# S7CAS-PLEIADES-CARTE-MERE_P01_DDR3.net
KiCad netlist of a schematic drawn in Altium Designer
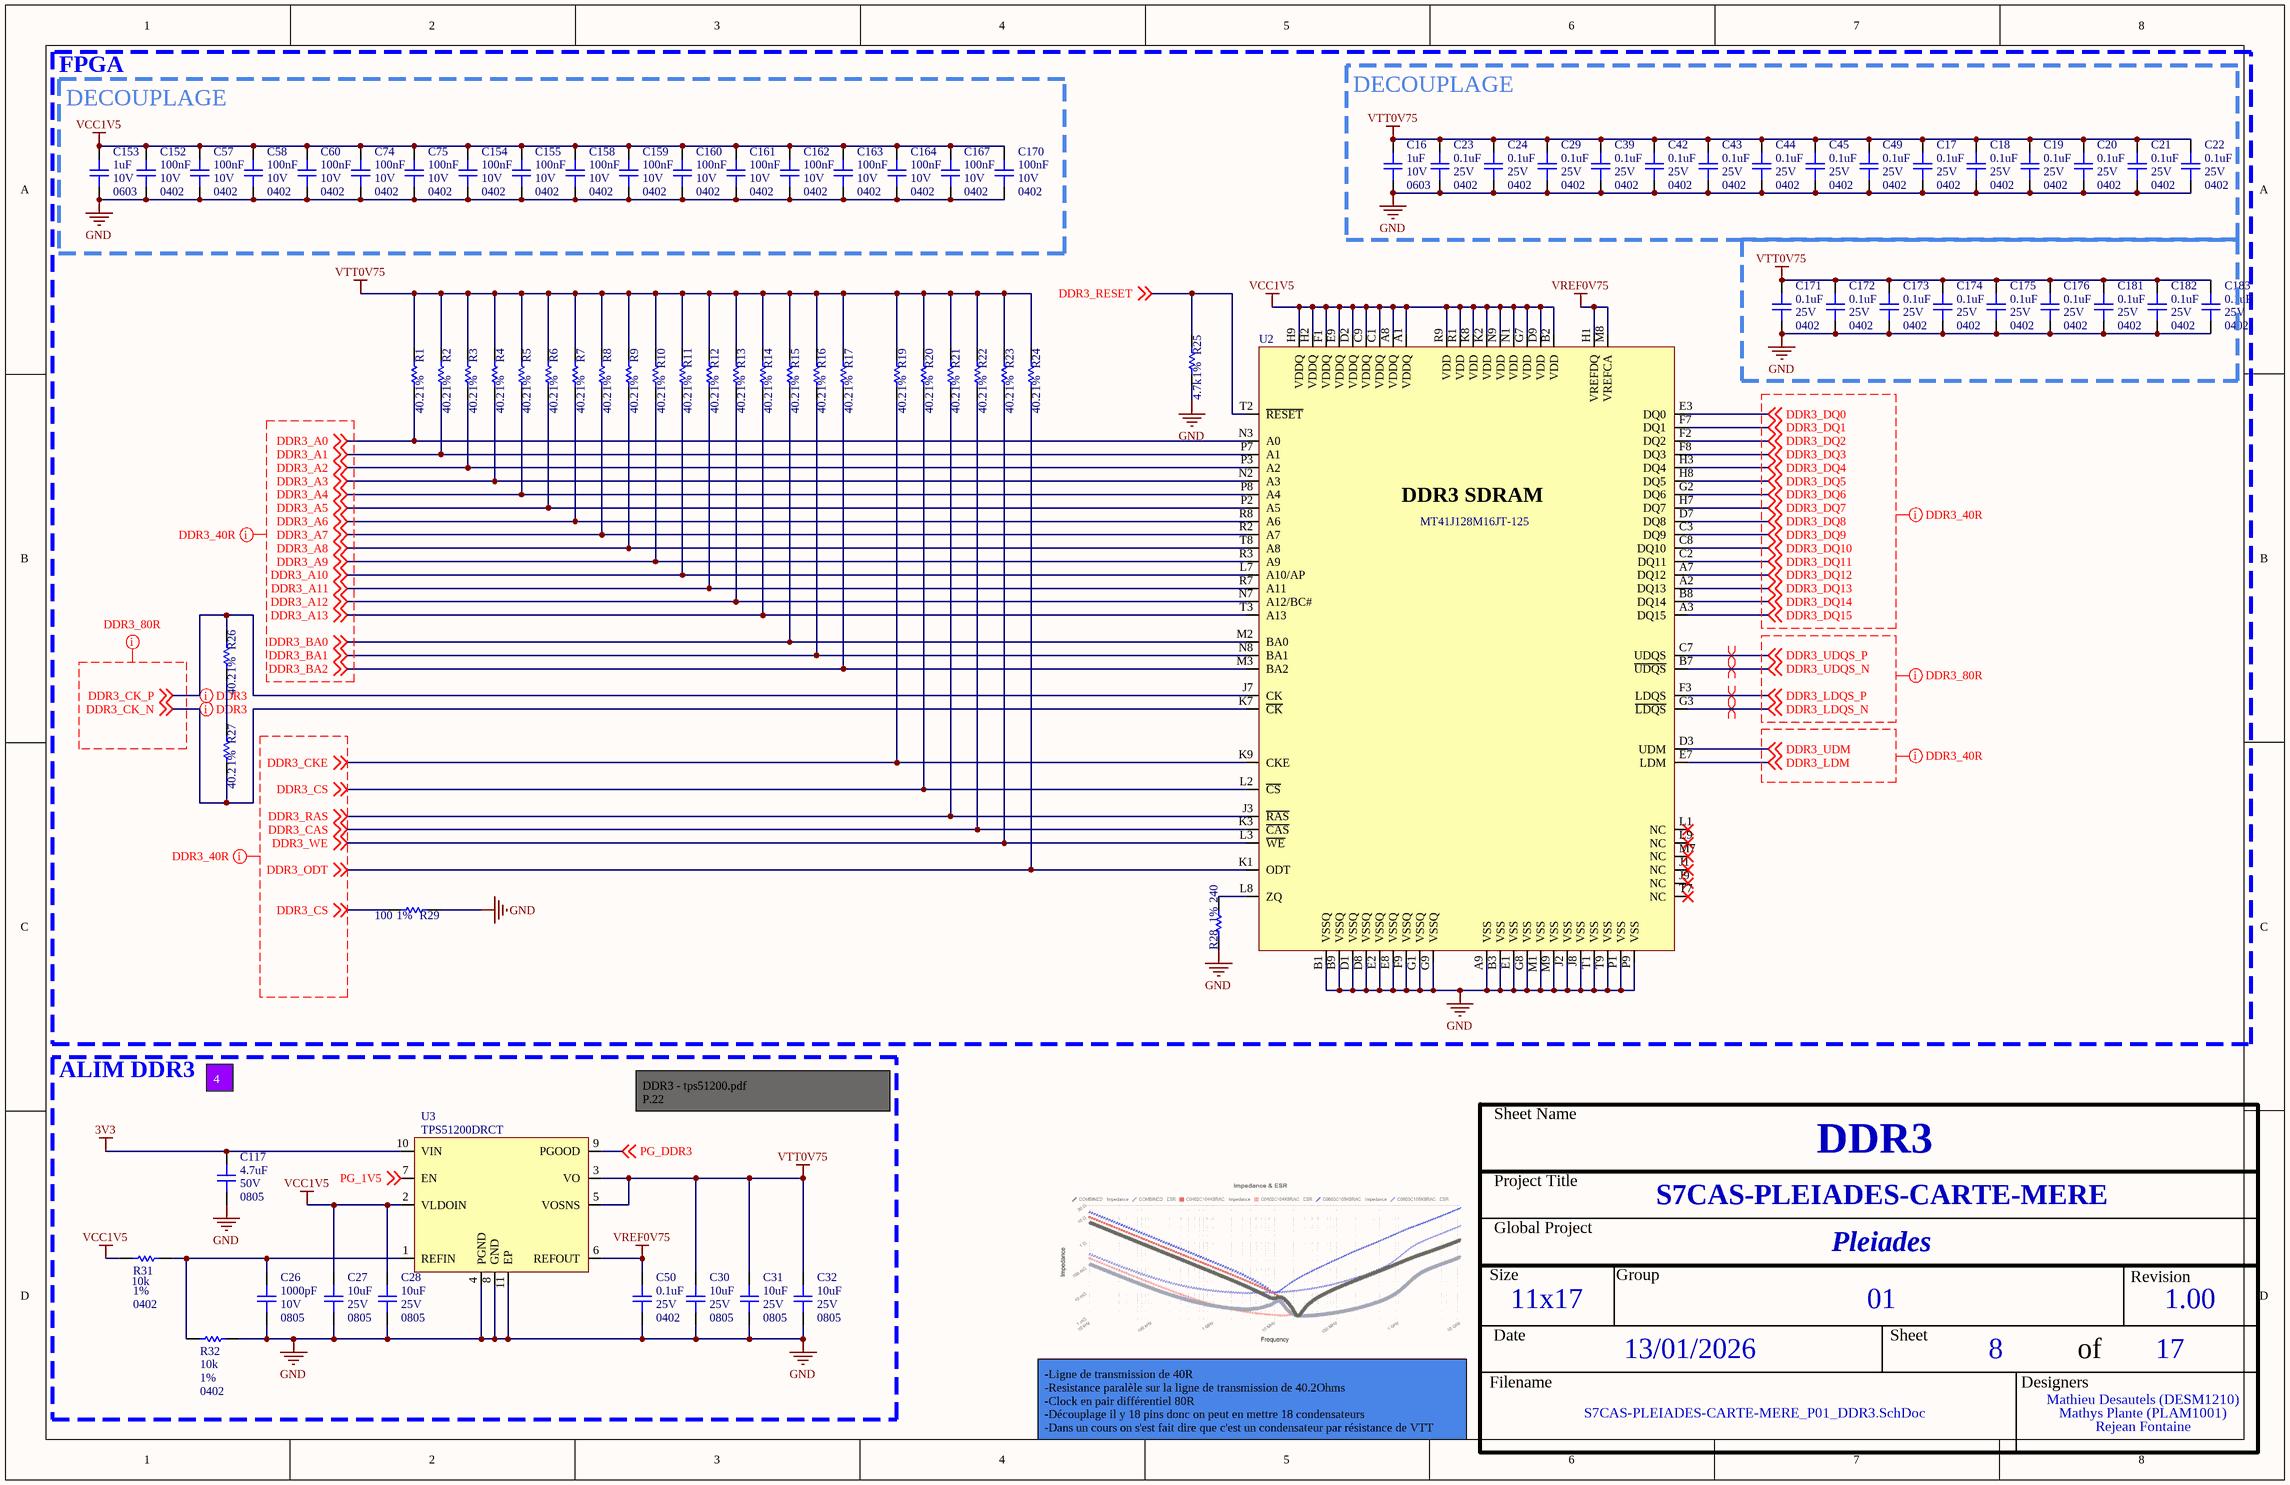
[diagram p0: S7CAS-PLEIADES-CARTE-MERE_P01_DDR3.SchDoc]

(export (version "E")
  (design (tool "Eeschema 10.0.6"))
  (components
    (comp (ref "C16")
      (value "1uF")
      (footprint "CAP_0603")
      (description "CAP - 0603")
      (fields
        (field (name "MFG PART NUMBER") "C0603C105K8RAC")
        (field (name "VOLTAGE") "10V")
        (field (name "PACKAGE") "0603")
        (field (name "CREATEDBY") "Jonathan Bouchard")
      )
      (libsource (lib "s7cas_lib2023") (part "CAP - 0603"))
    )
    (comp (ref "C17")
      (value "0.1uF")
      (footprint "CAP_0402")
      (description "0.1 µF ±10% 25V Ceramic Capacitor X7R 0402 (1005 Metric)")
      (fields
        (field (name "MFG") "Samsung Electro-Mechanics")
        (field (name "MFG PART NUMBER") "CL05B104KA5NNNC")
        (field (name "VOLTAGE") "25V")
        (field (name "PACKAGE") "0402")
        (field (name "CREATEDBY") "Jonathan Bouchard")
      )
      (libsource (lib "s7cas_lib2023") (part "CAP - 0402"))
    )
    (comp (ref "C18")
      (value "0.1uF")
      (footprint "CAP_0402")
      (description "0.1 µF ±10% 25V Ceramic Capacitor X7R 0402 (1005 Metric)")
      (fields
        (field (name "MFG") "Samsung Electro-Mechanics")
        (field (name "MFG PART NUMBER") "CL05B104KA5NNNC")
        (field (name "VOLTAGE") "25V")
        (field (name "PACKAGE") "0402")
        (field (name "CREATEDBY") "Jonathan Bouchard")
      )
      (libsource (lib "s7cas_lib2023") (part "CAP - 0402"))
    )
    (comp (ref "C19")
      (value "0.1uF")
      (footprint "CAP_0402")
      (description "0.1 µF ±10% 25V Ceramic Capacitor X7R 0402 (1005 Metric)")
      (fields
        (field (name "MFG") "Samsung Electro-Mechanics")
        (field (name "MFG PART NUMBER") "CL05B104KA5NNNC")
        (field (name "VOLTAGE") "25V")
        (field (name "PACKAGE") "0402")
        (field (name "CREATEDBY") "Jonathan Bouchard")
      )
      (libsource (lib "s7cas_lib2023") (part "CAP - 0402"))
    )
    (comp (ref "C20")
      (value "0.1uF")
      (footprint "CAP_0402")
      (description "0.1 µF ±10% 25V Ceramic Capacitor X7R 0402 (1005 Metric)")
      (fields
        (field (name "MFG") "Samsung Electro-Mechanics")
        (field (name "MFG PART NUMBER") "CL05B104KA5NNNC")
        (field (name "VOLTAGE") "25V")
        (field (name "PACKAGE") "0402")
        (field (name "CREATEDBY") "Jonathan Bouchard")
      )
      (libsource (lib "s7cas_lib2023") (part "CAP - 0402"))
    )
    (comp (ref "C21")
      (value "0.1uF")
      (footprint "CAP_0402")
      (description "0.1 µF ±10% 25V Ceramic Capacitor X7R 0402 (1005 Metric)")
      (fields
        (field (name "MFG") "Samsung Electro-Mechanics")
        (field (name "MFG PART NUMBER") "CL05B104KA5NNNC")
        (field (name "VOLTAGE") "25V")
        (field (name "PACKAGE") "0402")
        (field (name "CREATEDBY") "Jonathan Bouchard")
      )
      (libsource (lib "s7cas_lib2023") (part "CAP - 0402"))
    )
    (comp (ref "C22")
      (value "0.1uF")
      (footprint "CAP_0402")
      (description "0.1 µF ±10% 25V Ceramic Capacitor X7R 0402 (1005 Metric)")
      (fields
        (field (name "MFG") "Samsung Electro-Mechanics")
        (field (name "MFG PART NUMBER") "CL05B104KA5NNNC")
        (field (name "VOLTAGE") "25V")
        (field (name "PACKAGE") "0402")
        (field (name "CREATEDBY") "Jonathan Bouchard")
      )
      (libsource (lib "s7cas_lib2023") (part "CAP - 0402"))
    )
    (comp (ref "C23")
      (value "0.1uF")
      (footprint "CAP_0402")
      (description "0.1 µF ±10% 25V Ceramic Capacitor X7R 0402 (1005 Metric)")
      (fields
        (field (name "MFG") "Samsung Electro-Mechanics")
        (field (name "MFG PART NUMBER") "CL05B104KA5NNNC")
        (field (name "VOLTAGE") "25V")
        (field (name "PACKAGE") "0402")
        (field (name "CREATEDBY") "Jonathan Bouchard")
      )
      (libsource (lib "s7cas_lib2023") (part "CAP - 0402"))
    )
    (comp (ref "C24")
      (value "0.1uF")
      (footprint "CAP_0402")
      (description "0.1 µF ±10% 25V Ceramic Capacitor X7R 0402 (1005 Metric)")
      (fields
        (field (name "MFG") "Samsung Electro-Mechanics")
        (field (name "MFG PART NUMBER") "CL05B104KA5NNNC")
        (field (name "VOLTAGE") "25V")
        (field (name "PACKAGE") "0402")
        (field (name "CREATEDBY") "Jonathan Bouchard")
      )
      (libsource (lib "s7cas_lib2023") (part "CAP - 0402"))
    )
    (comp (ref "C26")
      (value "1000pF")
      (footprint "CAP_0805")
      (description "1000 pF ±10% 10V Ceramic Capacitor X7R 0805 (2012 Metric)")
      (fields
        (field (name "MFG PART NUMBER") "C0805C102K8RACTU")
        (field (name "VOLTAGE") "10V")
        (field (name "PACKAGE") "0805")
        (field (name "Comment") "CAP - 0805")
        (field (name "CREATEDBY") "Jonathan Bouchard")
      )
      (libsource (lib "s7cas_lib2023") (part "CAP - 0805"))
    )
    (comp (ref "C27")
      (value "10uF")
      (footprint "CAP_0805")
      (description "10 µF ±10% 25V Ceramic Capacitor X5R 0805 (2012 Metric)")
      (fields
        (field (name "MFG") "Samsung Electro-Mechanics")
        (field (name "MFG PART NUMBER") "CL21A106KAYNNNE")
        (field (name "VOLTAGE") "25V")
        (field (name "PACKAGE") "0805")
        (field (name "CREATEDBY") "Jonathan Bouchard")
      )
      (libsource (lib "s7cas_lib2023") (part "CAP - 0805"))
    )
    (comp (ref "C28")
      (value "10uF")
      (footprint "CAP_0805")
      (description "10 µF ±10% 25V Ceramic Capacitor X5R 0805 (2012 Metric)")
      (fields
        (field (name "MFG") "Samsung Electro-Mechanics")
        (field (name "MFG PART NUMBER") "CL21A106KAYNNNE")
        (field (name "VOLTAGE") "25V")
        (field (name "PACKAGE") "0805")
        (field (name "CREATEDBY") "Jonathan Bouchard")
      )
      (libsource (lib "s7cas_lib2023") (part "CAP - 0805"))
    )
    (comp (ref "C29")
      (value "0.1uF")
      (footprint "CAP_0402")
      (description "0.1 µF ±10% 25V Ceramic Capacitor X7R 0402 (1005 Metric)")
      (fields
        (field (name "MFG") "Samsung Electro-Mechanics")
        (field (name "MFG PART NUMBER") "CL05B104KA5NNNC")
        (field (name "VOLTAGE") "25V")
        (field (name "PACKAGE") "0402")
        (field (name "CREATEDBY") "Jonathan Bouchard")
      )
      (libsource (lib "s7cas_lib2023") (part "CAP - 0402"))
    )
    (comp (ref "C30")
      (value "10uF")
      (footprint "CAP_0805")
      (description "10 µF ±10% 25V Ceramic Capacitor X5R 0805 (2012 Metric)")
      (fields
        (field (name "MFG") "Samsung Electro-Mechanics")
        (field (name "MFG PART NUMBER") "CL21A106KAYNNNE")
        (field (name "VOLTAGE") "25V")
        (field (name "PACKAGE") "0805")
        (field (name "CREATEDBY") "Jonathan Bouchard")
      )
      (libsource (lib "s7cas_lib2023") (part "CAP - 0805"))
    )
    (comp (ref "C31")
      (value "10uF")
      (footprint "CAP_0805")
      (description "10 µF ±10% 25V Ceramic Capacitor X5R 0805 (2012 Metric)")
      (fields
        (field (name "MFG") "Samsung Electro-Mechanics")
        (field (name "MFG PART NUMBER") "CL21A106KAYNNNE")
        (field (name "VOLTAGE") "25V")
        (field (name "PACKAGE") "0805")
        (field (name "CREATEDBY") "Jonathan Bouchard")
      )
      (libsource (lib "s7cas_lib2023") (part "CAP - 0805"))
    )
    (comp (ref "C32")
      (value "10uF")
      (footprint "CAP_0805")
      (description "10 µF ±10% 25V Ceramic Capacitor X5R 0805 (2012 Metric)")
      (fields
        (field (name "MFG") "Samsung Electro-Mechanics")
        (field (name "MFG PART NUMBER") "CL21A106KAYNNNE")
        (field (name "VOLTAGE") "25V")
        (field (name "PACKAGE") "0805")
        (field (name "CREATEDBY") "Jonathan Bouchard")
      )
      (libsource (lib "s7cas_lib2023") (part "CAP - 0805"))
    )
    (comp (ref "C39")
      (value "0.1uF")
      (footprint "CAP_0402")
      (description "0.1 µF ±10% 25V Ceramic Capacitor X7R 0402 (1005 Metric)")
      (fields
        (field (name "MFG") "Samsung Electro-Mechanics")
        (field (name "MFG PART NUMBER") "CL05B104KA5NNNC")
        (field (name "VOLTAGE") "25V")
        (field (name "PACKAGE") "0402")
        (field (name "CREATEDBY") "Jonathan Bouchard")
      )
      (libsource (lib "s7cas_lib2023") (part "CAP - 0402"))
    )
    (comp (ref "C42")
      (value "0.1uF")
      (footprint "CAP_0402")
      (description "0.1 µF ±10% 25V Ceramic Capacitor X7R 0402 (1005 Metric)")
      (fields
        (field (name "MFG") "Samsung Electro-Mechanics")
        (field (name "MFG PART NUMBER") "CL05B104KA5NNNC")
        (field (name "VOLTAGE") "25V")
        (field (name "PACKAGE") "0402")
        (field (name "CREATEDBY") "Jonathan Bouchard")
      )
      (libsource (lib "s7cas_lib2023") (part "CAP - 0402"))
    )
    (comp (ref "C43")
      (value "0.1uF")
      (footprint "CAP_0402")
      (description "0.1 µF ±10% 25V Ceramic Capacitor X7R 0402 (1005 Metric)")
      (fields
        (field (name "MFG") "Samsung Electro-Mechanics")
        (field (name "MFG PART NUMBER") "CL05B104KA5NNNC")
        (field (name "VOLTAGE") "25V")
        (field (name "PACKAGE") "0402")
        (field (name "CREATEDBY") "Jonathan Bouchard")
      )
      (libsource (lib "s7cas_lib2023") (part "CAP - 0402"))
    )
    (comp (ref "C44")
      (value "0.1uF")
      (footprint "CAP_0402")
      (description "0.1 µF ±10% 25V Ceramic Capacitor X7R 0402 (1005 Metric)")
      (fields
        (field (name "MFG") "Samsung Electro-Mechanics")
        (field (name "MFG PART NUMBER") "CL05B104KA5NNNC")
        (field (name "VOLTAGE") "25V")
        (field (name "PACKAGE") "0402")
        (field (name "CREATEDBY") "Jonathan Bouchard")
      )
      (libsource (lib "s7cas_lib2023") (part "CAP - 0402"))
    )
    (comp (ref "C45")
      (value "0.1uF")
      (footprint "CAP_0402")
      (description "0.1 µF ±10% 25V Ceramic Capacitor X7R 0402 (1005 Metric)")
      (fields
        (field (name "MFG") "Samsung Electro-Mechanics")
        (field (name "MFG PART NUMBER") "CL05B104KA5NNNC")
        (field (name "VOLTAGE") "25V")
        (field (name "PACKAGE") "0402")
        (field (name "CREATEDBY") "Jonathan Bouchard")
      )
      (libsource (lib "s7cas_lib2023") (part "CAP - 0402"))
    )
    (comp (ref "C49")
      (value "0.1uF")
      (footprint "CAP_0402")
      (description "0.1 µF ±10% 25V Ceramic Capacitor X7R 0402 (1005 Metric)")
      (fields
        (field (name "MFG") "Samsung Electro-Mechanics")
        (field (name "MFG PART NUMBER") "CL05B104KA5NNNC")
        (field (name "VOLTAGE") "25V")
        (field (name "PACKAGE") "0402")
        (field (name "CREATEDBY") "Jonathan Bouchard")
      )
      (libsource (lib "s7cas_lib2023") (part "CAP - 0402"))
    )
    (comp (ref "C50")
      (value "0.1uF")
      (footprint "CAP_0402")
      (description "0.1 µF ±10% 25V Ceramic Capacitor X7R 0402 (1005 Metric)")
      (fields
        (field (name "MFG") "Samsung Electro-Mechanics")
        (field (name "MFG PART NUMBER") "CL05B104KA5NNNC")
        (field (name "VOLTAGE") "25V")
        (field (name "PACKAGE") "0402")
        (field (name "CREATEDBY") "Jonathan Bouchard")
      )
      (libsource (lib "s7cas_lib2023") (part "CAP - 0402"))
    )
    (comp (ref "C57")
      (value "100nF")
      (footprint "CAP_0402")
      (description "CAP - 0402")
      (fields
        (field (name "MFG PART NUMBER") "C0402C104K8RAC")
        (field (name "VOLTAGE") "10V")
        (field (name "PACKAGE") "0402")
        (field (name "CREATEDBY") "Jonathan Bouchard")
      )
      (libsource (lib "s7cas_lib2023") (part "CAP - 0402"))
    )
    (comp (ref "C58")
      (value "100nF")
      (footprint "CAP_0402")
      (description "CAP - 0402")
      (fields
        (field (name "MFG PART NUMBER") "C0402C104K8RAC")
        (field (name "VOLTAGE") "10V")
        (field (name "PACKAGE") "0402")
        (field (name "CREATEDBY") "Jonathan Bouchard")
      )
      (libsource (lib "s7cas_lib2023") (part "CAP - 0402"))
    )
    (comp (ref "C60")
      (value "100nF")
      (footprint "CAP_0402")
      (description "CAP - 0402")
      (fields
        (field (name "MFG PART NUMBER") "C0402C104K8RAC")
        (field (name "VOLTAGE") "10V")
        (field (name "PACKAGE") "0402")
        (field (name "CREATEDBY") "Jonathan Bouchard")
      )
      (libsource (lib "s7cas_lib2023") (part "CAP - 0402"))
    )
    (comp (ref "C74")
      (value "100nF")
      (footprint "CAP_0402")
      (description "CAP - 0402")
      (fields
        (field (name "MFG PART NUMBER") "C0402C104K8RAC")
        (field (name "VOLTAGE") "10V")
        (field (name "PACKAGE") "0402")
        (field (name "CREATEDBY") "Jonathan Bouchard")
      )
      (libsource (lib "s7cas_lib2023") (part "CAP - 0402"))
    )
    (comp (ref "C75")
      (value "100nF")
      (footprint "CAP_0402")
      (description "CAP - 0402")
      (fields
        (field (name "MFG PART NUMBER") "C0402C104K8RAC")
        (field (name "VOLTAGE") "10V")
        (field (name "PACKAGE") "0402")
        (field (name "CREATEDBY") "Jonathan Bouchard")
      )
      (libsource (lib "s7cas_lib2023") (part "CAP - 0402"))
    )
    (comp (ref "C117")
      (value "4.7uF")
      (footprint "CAP_0805")
      (description "4.7 µF ±10% 50V Ceramic Capacitor X5R 0805 (2012 Metric)")
      (fields
        (field (name "MFG") "Murata Electronics")
        (field (name "MFG PART NUMBER") "GRT21BR61H475KE13L")
        (field (name "VOLTAGE") "50V")
        (field (name "PACKAGE") "0805")
        (field (name "CREATEDBY") "Jonathan Bouchard")
      )
      (libsource (lib "s7cas_lib2023") (part "CAP - 0805"))
    )
    (comp (ref "C152")
      (value "100nF")
      (footprint "CAP_0402")
      (description "CAP - 0402")
      (fields
        (field (name "MFG PART NUMBER") "C0402C104K8RAC")
        (field (name "VOLTAGE") "10V")
        (field (name "PACKAGE") "0402")
        (field (name "CREATEDBY") "Jonathan Bouchard")
      )
      (libsource (lib "s7cas_lib2023") (part "CAP - 0402"))
    )
    (comp (ref "C153")
      (value "1uF")
      (footprint "CAP_0603")
      (description "CAP - 0603")
      (fields
        (field (name "MFG PART NUMBER") "C0603C105K8RAC")
        (field (name "VOLTAGE") "10V")
        (field (name "PACKAGE") "0603")
        (field (name "CREATEDBY") "Jonathan Bouchard")
      )
      (libsource (lib "s7cas_lib2023") (part "CAP - 0603"))
    )
    (comp (ref "C154")
      (value "100nF")
      (footprint "CAP_0402")
      (description "CAP - 0402")
      (fields
        (field (name "MFG PART NUMBER") "C0402C104K8RAC")
        (field (name "VOLTAGE") "10V")
        (field (name "PACKAGE") "0402")
        (field (name "CREATEDBY") "Jonathan Bouchard")
      )
      (libsource (lib "s7cas_lib2023") (part "CAP - 0402"))
    )
    (comp (ref "C155")
      (value "100nF")
      (footprint "CAP_0402")
      (description "CAP - 0402")
      (fields
        (field (name "MFG PART NUMBER") "C0402C104K8RAC")
        (field (name "VOLTAGE") "10V")
        (field (name "PACKAGE") "0402")
        (field (name "CREATEDBY") "Jonathan Bouchard")
      )
      (libsource (lib "s7cas_lib2023") (part "CAP - 0402"))
    )
    (comp (ref "C158")
      (value "100nF")
      (footprint "CAP_0402")
      (description "CAP - 0402")
      (fields
        (field (name "MFG PART NUMBER") "C0402C104K8RAC")
        (field (name "VOLTAGE") "10V")
        (field (name "PACKAGE") "0402")
        (field (name "CREATEDBY") "Jonathan Bouchard")
      )
      (libsource (lib "s7cas_lib2023") (part "CAP - 0402"))
    )
    (comp (ref "C159")
      (value "100nF")
      (footprint "CAP_0402")
      (description "CAP - 0402")
      (fields
        (field (name "MFG PART NUMBER") "C0402C104K8RAC")
        (field (name "VOLTAGE") "10V")
        (field (name "PACKAGE") "0402")
        (field (name "CREATEDBY") "Jonathan Bouchard")
      )
      (libsource (lib "s7cas_lib2023") (part "CAP - 0402"))
    )
    (comp (ref "C160")
      (value "100nF")
      (footprint "CAP_0402")
      (description "CAP - 0402")
      (fields
        (field (name "MFG PART NUMBER") "C0402C104K8RAC")
        (field (name "VOLTAGE") "10V")
        (field (name "PACKAGE") "0402")
        (field (name "CREATEDBY") "Jonathan Bouchard")
      )
      (libsource (lib "s7cas_lib2023") (part "CAP - 0402"))
    )
    (comp (ref "C161")
      (value "100nF")
      (footprint "CAP_0402")
      (description "CAP - 0402")
      (fields
        (field (name "MFG PART NUMBER") "C0402C104K8RAC")
        (field (name "VOLTAGE") "10V")
        (field (name "PACKAGE") "0402")
        (field (name "CREATEDBY") "Jonathan Bouchard")
      )
      (libsource (lib "s7cas_lib2023") (part "CAP - 0402"))
    )
    (comp (ref "C162")
      (value "100nF")
      (footprint "CAP_0402")
      (description "CAP - 0402")
      (fields
        (field (name "MFG PART NUMBER") "C0402C104K8RAC")
        (field (name "VOLTAGE") "10V")
        (field (name "PACKAGE") "0402")
        (field (name "CREATEDBY") "Jonathan Bouchard")
      )
      (libsource (lib "s7cas_lib2023") (part "CAP - 0402"))
    )
    (comp (ref "C163")
      (value "100nF")
      (footprint "CAP_0402")
      (description "CAP - 0402")
      (fields
        (field (name "MFG PART NUMBER") "C0402C104K8RAC")
        (field (name "VOLTAGE") "10V")
        (field (name "PACKAGE") "0402")
        (field (name "CREATEDBY") "Jonathan Bouchard")
      )
      (libsource (lib "s7cas_lib2023") (part "CAP - 0402"))
    )
    (comp (ref "C164")
      (value "100nF")
      (footprint "CAP_0402")
      (description "CAP - 0402")
      (fields
        (field (name "MFG PART NUMBER") "C0402C104K8RAC")
        (field (name "VOLTAGE") "10V")
        (field (name "PACKAGE") "0402")
        (field (name "CREATEDBY") "Jonathan Bouchard")
      )
      (libsource (lib "s7cas_lib2023") (part "CAP - 0402"))
    )
    (comp (ref "C167")
      (value "100nF")
      (footprint "CAP_0402")
      (description "CAP - 0402")
      (fields
        (field (name "MFG PART NUMBER") "C0402C104K8RAC")
        (field (name "VOLTAGE") "10V")
        (field (name "PACKAGE") "0402")
        (field (name "CREATEDBY") "Jonathan Bouchard")
      )
      (libsource (lib "s7cas_lib2023") (part "CAP - 0402"))
    )
    (comp (ref "C170")
      (value "100nF")
      (footprint "CAP_0402")
      (description "CAP - 0402")
      (fields
        (field (name "MFG PART NUMBER") "C0402C104K8RAC")
        (field (name "VOLTAGE") "10V")
        (field (name "PACKAGE") "0402")
        (field (name "CREATEDBY") "Jonathan Bouchard")
      )
      (libsource (lib "s7cas_lib2023") (part "CAP - 0402"))
    )
    (comp (ref "C171")
      (value "0.1uF")
      (footprint "CAP_0402")
      (description "0.1 µF ±10% 25V Ceramic Capacitor X7R 0402 (1005 Metric)")
      (fields
        (field (name "MFG") "Samsung Electro-Mechanics")
        (field (name "MFG PART NUMBER") "CL05B104KA5NNNC")
        (field (name "VOLTAGE") "25V")
        (field (name "PACKAGE") "0402")
        (field (name "CREATEDBY") "Jonathan Bouchard")
      )
      (libsource (lib "s7cas_lib2023") (part "CAP - 0402"))
    )
    (comp (ref "C172")
      (value "0.1uF")
      (footprint "CAP_0402")
      (description "0.1 µF ±10% 25V Ceramic Capacitor X7R 0402 (1005 Metric)")
      (fields
        (field (name "MFG") "Samsung Electro-Mechanics")
        (field (name "MFG PART NUMBER") "CL05B104KA5NNNC")
        (field (name "VOLTAGE") "25V")
        (field (name "PACKAGE") "0402")
        (field (name "CREATEDBY") "Jonathan Bouchard")
      )
      (libsource (lib "s7cas_lib2023") (part "CAP - 0402"))
    )
    (comp (ref "C173")
      (value "0.1uF")
      (footprint "CAP_0402")
      (description "0.1 µF ±10% 25V Ceramic Capacitor X7R 0402 (1005 Metric)")
      (fields
        (field (name "MFG") "Samsung Electro-Mechanics")
        (field (name "MFG PART NUMBER") "CL05B104KA5NNNC")
        (field (name "VOLTAGE") "25V")
        (field (name "PACKAGE") "0402")
        (field (name "CREATEDBY") "Jonathan Bouchard")
      )
      (libsource (lib "s7cas_lib2023") (part "CAP - 0402"))
    )
    (comp (ref "C174")
      (value "0.1uF")
      (footprint "CAP_0402")
      (description "0.1 µF ±10% 25V Ceramic Capacitor X7R 0402 (1005 Metric)")
      (fields
        (field (name "MFG") "Samsung Electro-Mechanics")
        (field (name "MFG PART NUMBER") "CL05B104KA5NNNC")
        (field (name "VOLTAGE") "25V")
        (field (name "PACKAGE") "0402")
        (field (name "CREATEDBY") "Jonathan Bouchard")
      )
      (libsource (lib "s7cas_lib2023") (part "CAP - 0402"))
    )
    (comp (ref "C175")
      (value "0.1uF")
      (footprint "CAP_0402")
      (description "0.1 µF ±10% 25V Ceramic Capacitor X7R 0402 (1005 Metric)")
      (fields
        (field (name "MFG") "Samsung Electro-Mechanics")
        (field (name "MFG PART NUMBER") "CL05B104KA5NNNC")
        (field (name "VOLTAGE") "25V")
        (field (name "PACKAGE") "0402")
        (field (name "CREATEDBY") "Jonathan Bouchard")
      )
      (libsource (lib "s7cas_lib2023") (part "CAP - 0402"))
    )
    (comp (ref "C176")
      (value "0.1uF")
      (footprint "CAP_0402")
      (description "0.1 µF ±10% 25V Ceramic Capacitor X7R 0402 (1005 Metric)")
      (fields
        (field (name "MFG") "Samsung Electro-Mechanics")
        (field (name "MFG PART NUMBER") "CL05B104KA5NNNC")
        (field (name "VOLTAGE") "25V")
        (field (name "PACKAGE") "0402")
        (field (name "CREATEDBY") "Jonathan Bouchard")
      )
      (libsource (lib "s7cas_lib2023") (part "CAP - 0402"))
    )
    (comp (ref "C181")
      (value "0.1uF")
      (footprint "CAP_0402")
      (description "0.1 µF ±10% 25V Ceramic Capacitor X7R 0402 (1005 Metric)")
      (fields
        (field (name "MFG") "Samsung Electro-Mechanics")
        (field (name "MFG PART NUMBER") "CL05B104KA5NNNC")
        (field (name "VOLTAGE") "25V")
        (field (name "PACKAGE") "0402")
        (field (name "CREATEDBY") "Jonathan Bouchard")
      )
      (libsource (lib "s7cas_lib2023") (part "CAP - 0402"))
    )
    (comp (ref "C182")
      (value "0.1uF")
      (footprint "CAP_0402")
      (description "0.1 µF ±10% 25V Ceramic Capacitor X7R 0402 (1005 Metric)")
      (fields
        (field (name "MFG") "Samsung Electro-Mechanics")
        (field (name "MFG PART NUMBER") "CL05B104KA5NNNC")
        (field (name "VOLTAGE") "25V")
        (field (name "PACKAGE") "0402")
        (field (name "CREATEDBY") "Jonathan Bouchard")
      )
      (libsource (lib "s7cas_lib2023") (part "CAP - 0402"))
    )
    (comp (ref "C183")
      (value "0.1uF")
      (footprint "CAP_0402")
      (description "0.1 µF ±10% 25V Ceramic Capacitor X7R 0402 (1005 Metric)")
      (fields
        (field (name "MFG") "Samsung Electro-Mechanics")
        (field (name "MFG PART NUMBER") "CL05B104KA5NNNC")
        (field (name "VOLTAGE") "25V")
        (field (name "PACKAGE") "0402")
        (field (name "CREATEDBY") "Jonathan Bouchard")
      )
      (libsource (lib "s7cas_lib2023") (part "CAP - 0402"))
    )
    (comp (ref "R1")
      (value "40.2")
      (footprint "RES_0402")
      (description "40.2 Ohms ±1% 0.1W, 1/10W Chip Resistor 0402 (1005 Metric) Automotive AEC-Q200 Thick Film")
      (fields
        (field (name "VOLTAGE") "75V")
        (field (name "MFG PART NUMBER") "CRCW040240R2FKED")
        (field (name "PRECISION") "1%")
        (field (name "CREATEDBY") "Jonathan Bouchard")
      )
      (libsource (lib "s7cas_lib2023") (part "RES - 0402"))
    )
    (comp (ref "R2")
      (value "40.2")
      (footprint "RES_0402")
      (description "40.2 Ohms ±1% 0.1W, 1/10W Chip Resistor 0402 (1005 Metric) Automotive AEC-Q200 Thick Film")
      (fields
        (field (name "VOLTAGE") "75V")
        (field (name "MFG PART NUMBER") "CRCW040240R2FKED")
        (field (name "PRECISION") "1%")
        (field (name "CREATEDBY") "Jonathan Bouchard")
      )
      (libsource (lib "s7cas_lib2023") (part "RES - 0402"))
    )
    (comp (ref "R3")
      (value "40.2")
      (footprint "RES_0402")
      (description "40.2 Ohms ±1% 0.1W, 1/10W Chip Resistor 0402 (1005 Metric) Automotive AEC-Q200 Thick Film")
      (fields
        (field (name "VOLTAGE") "75V")
        (field (name "MFG PART NUMBER") "CRCW040240R2FKED")
        (field (name "PRECISION") "1%")
        (field (name "CREATEDBY") "Jonathan Bouchard")
      )
      (libsource (lib "s7cas_lib2023") (part "RES - 0402"))
    )
    (comp (ref "R4")
      (value "40.2")
      (footprint "RES_0402")
      (description "40.2 Ohms ±1% 0.1W, 1/10W Chip Resistor 0402 (1005 Metric) Automotive AEC-Q200 Thick Film")
      (fields
        (field (name "VOLTAGE") "75V")
        (field (name "MFG PART NUMBER") "CRCW040240R2FKED")
        (field (name "PRECISION") "1%")
        (field (name "CREATEDBY") "Jonathan Bouchard")
      )
      (libsource (lib "s7cas_lib2023") (part "RES - 0402"))
    )
    (comp (ref "R5")
      (value "40.2")
      (footprint "RES_0402")
      (description "40.2 Ohms ±1% 0.1W, 1/10W Chip Resistor 0402 (1005 Metric) Automotive AEC-Q200 Thick Film")
      (fields
        (field (name "VOLTAGE") "75V")
        (field (name "MFG PART NUMBER") "CRCW040240R2FKED")
        (field (name "PRECISION") "1%")
        (field (name "CREATEDBY") "Jonathan Bouchard")
      )
      (libsource (lib "s7cas_lib2023") (part "RES - 0402"))
    )
    (comp (ref "R6")
      (value "40.2")
      (footprint "RES_0402")
      (description "40.2 Ohms ±1% 0.1W, 1/10W Chip Resistor 0402 (1005 Metric) Automotive AEC-Q200 Thick Film")
      (fields
        (field (name "VOLTAGE") "75V")
        (field (name "MFG PART NUMBER") "CRCW040240R2FKED")
        (field (name "PRECISION") "1%")
        (field (name "CREATEDBY") "Jonathan Bouchard")
      )
      (libsource (lib "s7cas_lib2023") (part "RES - 0402"))
    )
    (comp (ref "R7")
      (value "40.2")
      (footprint "RES_0402")
      (description "40.2 Ohms ±1% 0.1W, 1/10W Chip Resistor 0402 (1005 Metric) Automotive AEC-Q200 Thick Film")
      (fields
        (field (name "VOLTAGE") "75V")
        (field (name "MFG PART NUMBER") "CRCW040240R2FKED")
        (field (name "PRECISION") "1%")
        (field (name "CREATEDBY") "Jonathan Bouchard")
      )
      (libsource (lib "s7cas_lib2023") (part "RES - 0402"))
    )
    (comp (ref "R8")
      (value "40.2")
      (footprint "RES_0402")
      (description "40.2 Ohms ±1% 0.1W, 1/10W Chip Resistor 0402 (1005 Metric) Automotive AEC-Q200 Thick Film")
      (fields
        (field (name "VOLTAGE") "75V")
        (field (name "MFG PART NUMBER") "CRCW040240R2FKED")
        (field (name "PRECISION") "1%")
        (field (name "CREATEDBY") "Jonathan Bouchard")
      )
      (libsource (lib "s7cas_lib2023") (part "RES - 0402"))
    )
    (comp (ref "R9")
      (value "40.2")
      (footprint "RES_0402")
      (description "40.2 Ohms ±1% 0.1W, 1/10W Chip Resistor 0402 (1005 Metric) Automotive AEC-Q200 Thick Film")
      (fields
        (field (name "VOLTAGE") "75V")
        (field (name "MFG PART NUMBER") "CRCW040240R2FKED")
        (field (name "PRECISION") "1%")
        (field (name "CREATEDBY") "Jonathan Bouchard")
      )
      (libsource (lib "s7cas_lib2023") (part "RES - 0402"))
    )
    (comp (ref "R10")
      (value "40.2")
      (footprint "RES_0402")
      (description "40.2 Ohms ±1% 0.1W, 1/10W Chip Resistor 0402 (1005 Metric) Automotive AEC-Q200 Thick Film")
      (fields
        (field (name "VOLTAGE") "75V")
        (field (name "MFG PART NUMBER") "CRCW040240R2FKED")
        (field (name "PRECISION") "1%")
        (field (name "CREATEDBY") "Jonathan Bouchard")
      )
      (libsource (lib "s7cas_lib2023") (part "RES - 0402"))
    )
    (comp (ref "R11")
      (value "40.2")
      (footprint "RES_0402")
      (description "40.2 Ohms ±1% 0.1W, 1/10W Chip Resistor 0402 (1005 Metric) Automotive AEC-Q200 Thick Film")
      (fields
        (field (name "VOLTAGE") "75V")
        (field (name "MFG PART NUMBER") "CRCW040240R2FKED")
        (field (name "PRECISION") "1%")
        (field (name "CREATEDBY") "Jonathan Bouchard")
      )
      (libsource (lib "s7cas_lib2023") (part "RES - 0402"))
    )
    (comp (ref "R12")
      (value "40.2")
      (footprint "RES_0402")
      (description "40.2 Ohms ±1% 0.1W, 1/10W Chip Resistor 0402 (1005 Metric) Automotive AEC-Q200 Thick Film")
      (fields
        (field (name "VOLTAGE") "75V")
        (field (name "MFG PART NUMBER") "CRCW040240R2FKED")
        (field (name "PRECISION") "1%")
        (field (name "CREATEDBY") "Jonathan Bouchard")
      )
      (libsource (lib "s7cas_lib2023") (part "RES - 0402"))
    )
    (comp (ref "R13")
      (value "40.2")
      (footprint "RES_0402")
      (description "40.2 Ohms ±1% 0.1W, 1/10W Chip Resistor 0402 (1005 Metric) Automotive AEC-Q200 Thick Film")
      (fields
        (field (name "VOLTAGE") "75V")
        (field (name "MFG PART NUMBER") "CRCW040240R2FKED")
        (field (name "PRECISION") "1%")
        (field (name "CREATEDBY") "Jonathan Bouchard")
      )
      (libsource (lib "s7cas_lib2023") (part "RES - 0402"))
    )
    (comp (ref "R14")
      (value "40.2")
      (footprint "RES_0402")
      (description "40.2 Ohms ±1% 0.1W, 1/10W Chip Resistor 0402 (1005 Metric) Automotive AEC-Q200 Thick Film")
      (fields
        (field (name "VOLTAGE") "75V")
        (field (name "MFG PART NUMBER") "CRCW040240R2FKED")
        (field (name "PRECISION") "1%")
        (field (name "CREATEDBY") "Jonathan Bouchard")
      )
      (libsource (lib "s7cas_lib2023") (part "RES - 0402"))
    )
    (comp (ref "R15")
      (value "40.2")
      (footprint "RES_0402")
      (description "40.2 Ohms ±1% 0.1W, 1/10W Chip Resistor 0402 (1005 Metric) Automotive AEC-Q200 Thick Film")
      (fields
        (field (name "VOLTAGE") "75V")
        (field (name "MFG PART NUMBER") "CRCW040240R2FKED")
        (field (name "PRECISION") "1%")
        (field (name "CREATEDBY") "Jonathan Bouchard")
      )
      (libsource (lib "s7cas_lib2023") (part "RES - 0402"))
    )
    (comp (ref "R16")
      (value "40.2")
      (footprint "RES_0402")
      (description "40.2 Ohms ±1% 0.1W, 1/10W Chip Resistor 0402 (1005 Metric) Automotive AEC-Q200 Thick Film")
      (fields
        (field (name "VOLTAGE") "75V")
        (field (name "MFG PART NUMBER") "CRCW040240R2FKED")
        (field (name "PRECISION") "1%")
        (field (name "CREATEDBY") "Jonathan Bouchard")
      )
      (libsource (lib "s7cas_lib2023") (part "RES - 0402"))
    )
    (comp (ref "R17")
      (value "40.2")
      (footprint "RES_0402")
      (description "40.2 Ohms ±1% 0.1W, 1/10W Chip Resistor 0402 (1005 Metric) Automotive AEC-Q200 Thick Film")
      (fields
        (field (name "VOLTAGE") "75V")
        (field (name "MFG PART NUMBER") "CRCW040240R2FKED")
        (field (name "PRECISION") "1%")
        (field (name "CREATEDBY") "Jonathan Bouchard")
      )
      (libsource (lib "s7cas_lib2023") (part "RES - 0402"))
    )
    (comp (ref "R19")
      (value "40.2")
      (footprint "RES_0402")
      (description "40.2 Ohms ±1% 0.1W, 1/10W Chip Resistor 0402 (1005 Metric) Automotive AEC-Q200 Thick Film")
      (fields
        (field (name "VOLTAGE") "75V")
        (field (name "MFG PART NUMBER") "CRCW040240R2FKED")
        (field (name "PRECISION") "1%")
        (field (name "CREATEDBY") "Jonathan Bouchard")
      )
      (libsource (lib "s7cas_lib2023") (part "RES - 0402"))
    )
    (comp (ref "R20")
      (value "40.2")
      (footprint "RES_0402")
      (description "40.2 Ohms ±1% 0.1W, 1/10W Chip Resistor 0402 (1005 Metric) Automotive AEC-Q200 Thick Film")
      (fields
        (field (name "VOLTAGE") "75V")
        (field (name "MFG PART NUMBER") "CRCW040240R2FKED")
        (field (name "PRECISION") "1%")
        (field (name "CREATEDBY") "Jonathan Bouchard")
      )
      (libsource (lib "s7cas_lib2023") (part "RES - 0402"))
    )
    (comp (ref "R21")
      (value "40.2")
      (footprint "RES_0402")
      (description "40.2 Ohms ±1% 0.1W, 1/10W Chip Resistor 0402 (1005 Metric) Automotive AEC-Q200 Thick Film")
      (fields
        (field (name "VOLTAGE") "75V")
        (field (name "MFG PART NUMBER") "CRCW040240R2FKED")
        (field (name "PRECISION") "1%")
        (field (name "CREATEDBY") "Jonathan Bouchard")
      )
      (libsource (lib "s7cas_lib2023") (part "RES - 0402"))
    )
    (comp (ref "R22")
      (value "40.2")
      (footprint "RES_0402")
      (description "40.2 Ohms ±1% 0.1W, 1/10W Chip Resistor 0402 (1005 Metric) Automotive AEC-Q200 Thick Film")
      (fields
        (field (name "VOLTAGE") "75V")
        (field (name "MFG PART NUMBER") "CRCW040240R2FKED")
        (field (name "PRECISION") "1%")
        (field (name "CREATEDBY") "Jonathan Bouchard")
      )
      (libsource (lib "s7cas_lib2023") (part "RES - 0402"))
    )
    (comp (ref "R23")
      (value "40.2")
      (footprint "RES_0402")
      (description "40.2 Ohms ±1% 0.1W, 1/10W Chip Resistor 0402 (1005 Metric) Automotive AEC-Q200 Thick Film")
      (fields
        (field (name "VOLTAGE") "75V")
        (field (name "MFG PART NUMBER") "CRCW040240R2FKED")
        (field (name "PRECISION") "1%")
        (field (name "CREATEDBY") "Jonathan Bouchard")
      )
      (libsource (lib "s7cas_lib2023") (part "RES - 0402"))
    )
    (comp (ref "R24")
      (value "40.2")
      (footprint "RES_0402")
      (description "40.2 Ohms ±1% 0.1W, 1/10W Chip Resistor 0402 (1005 Metric) Automotive AEC-Q200 Thick Film")
      (fields
        (field (name "VOLTAGE") "75V")
        (field (name "MFG PART NUMBER") "CRCW040240R2FKED")
        (field (name "PRECISION") "1%")
        (field (name "CREATEDBY") "Jonathan Bouchard")
      )
      (libsource (lib "s7cas_lib2023") (part "RES - 0402"))
    )
    (comp (ref "R25")
      (value "4.7k")
      (footprint "RES_0402")
      (description "4.7 kOhms ±1% 0.063W, 1/16W Chip Resistor 0402 (1005 Metric) Moisture Resistant Thick Film")
      (fields
        (field (name "VOLTAGE") "75V")
        (field (name "MFG PART NUMBER") "RC0402FR-074K7L")
        (field (name "PRECISION") "1%")
        (field (name "CREATEDBY") "Jonathan Bouchard")
      )
      (libsource (lib "s7cas_lib2023") (part "RES - 0402"))
    )
    (comp (ref "R26")
      (value "40.2")
      (footprint "RES_0402")
      (description "40.2 Ohms ±1% 0.1W, 1/10W Chip Resistor 0402 (1005 Metric) Automotive AEC-Q200 Thick Film")
      (fields
        (field (name "VOLTAGE") "75V")
        (field (name "MFG PART NUMBER") "CRCW040240R2FKED")
        (field (name "PRECISION") "1%")
        (field (name "CREATEDBY") "Jonathan Bouchard")
      )
      (libsource (lib "s7cas_lib2023") (part "RES - 0402"))
    )
    (comp (ref "R27")
      (value "40.2")
      (footprint "RES_0402")
      (description "40.2 Ohms ±1% 0.1W, 1/10W Chip Resistor 0402 (1005 Metric) Automotive AEC-Q200 Thick Film")
      (fields
        (field (name "VOLTAGE") "75V")
        (field (name "MFG PART NUMBER") "CRCW040240R2FKED")
        (field (name "PRECISION") "1%")
        (field (name "CREATEDBY") "Jonathan Bouchard")
      )
      (libsource (lib "s7cas_lib2023") (part "RES - 0402"))
    )
    (comp (ref "R28")
      (value "240")
      (footprint "RES_0402")
      (description "240 Ohms ±1% 0.1W, 1/10W Chip Resistor 0402 (1005 Metric) Automotive AEC-Q200 Thick Film")
      (fields
        (field (name "VOLTAGE") "50V")
        (field (name "MFG PART NUMBER") "ERJ-2RKF2400X")
        (field (name "PRECISION") "1%")
        (field (name "CREATEDBY") "Jonathan Bouchard")
      )
      (libsource (lib "s7cas_lib2023") (part "RES - 0402"))
    )
    (comp (ref "R29")
      (value "100")
      (footprint "RES_0402")
      (description "100 Ohms ±1% 0.1W, 1/10W Chip Resistor 0402 (1005 Metric) Automotive AEC-Q200 Thick Film")
      (fields
        (field (name "VOLTAGE") "75V")
        (field (name "MFG PART NUMBER") "RK73H1ETTP1000F")
        (field (name "PRECISION") "1%")
        (field (name "CREATEDBY") "Jonathan Bouchard")
      )
      (libsource (lib "s7cas_lib2023") (part "RES - 0402"))
    )
    (comp (ref "R31")
      (value "10k")
      (footprint "RES_0402")
      (description "10 kOhms ±1% 0.063W, 1/16W Chip Resistor 0402 (1005 Metric) Automotive AEC-Q200 Thick Film")
      (fields
        (field (name "VOLTAGE") "75V")
        (field (name "MFG PART NUMBER") "RMCF0402FT10K0")
        (field (name "PACKAGE") "0402")
        (field (name "PRECISION") "1%")
        (field (name "CREATEDBY") "Jonathan Bouchard")
      )
      (libsource (lib "s7cas_lib2023") (part "RES - 0402"))
    )
    (comp (ref "R32")
      (value "10k")
      (footprint "RES_0402")
      (description "10 kOhms ±1% 0.063W, 1/16W Chip Resistor 0402 (1005 Metric) Automotive AEC-Q200 Thick Film")
      (fields
        (field (name "VOLTAGE") "75V")
        (field (name "MFG PART NUMBER") "RMCF0402FT10K0")
        (field (name "PACKAGE") "0402")
        (field (name "PRECISION") "1%")
        (field (name "CREATEDBY") "Jonathan Bouchard")
      )
      (libsource (lib "s7cas_lib2023") (part "RES - 0402"))
    )
    (comp (ref "U2")
      (value "MT41J128M16JT-125")
      (footprint "MEM_DDR3_MT41J128M16JT-125")
      (description "MEM - DDR3 SDRAM 2GBIT 800MHZ - TFBGA-96")
      (fields
        (field (name "VOLTAGE") "1.425 V ~ 1.575 V")
        (field (name "MFG") "Micrel")
        (field (name "CREATEDBY") "Jonathan Bouchard")
      )
      (libsource (lib "s7cas_lib2023") (part "MEM_DDR3_MT41J128M16JT-125{colon}K TR"))
    )
    (comp (ref "U3")
      (value "TPS51200DRCT")
      (footprint "REG_PMIC_TPS51200DRCT")
      (description "REG - DDR TERMINATION/REF REG - 10-VFDFN")
      (fields
        (field (name "CREATEDBY/DATE") "Joel Lemay 2019-03-19")
        (field (name "VERIFIEDBY") "Nicolas V. (2019-05-31)")
      )
      (libsource (lib "s7cas_lib2023") (part "REG_PMIC_TPS51200DRCT"))
    )
  )
  (nets
    (net (code "1") (name "3V3") (class "Default")
      (node (ref "C117") (pin "2") (pinfunction "2_2") (pintype "passive"))
      (node (ref "U3") (pin "10") (pinfunction "VIN_10") (pintype "passive"))
    )
    (net (code "2") (name "DDR3_A0") (class "Default")
      (node (ref "R1") (pin "1") (pinfunction "1_1") (pintype "passive"))
      (node (ref "U2") (pin "N3") (pinfunction "A0_N3") (pintype "passive"))
    )
    (net (code "3") (name "DDR3_A1") (class "Default")
      (node (ref "R2") (pin "1") (pinfunction "1_1") (pintype "passive"))
      (node (ref "U2") (pin "P7") (pinfunction "A1_P7") (pintype "passive"))
    )
    (net (code "4") (name "DDR3_A2") (class "Default")
      (node (ref "R3") (pin "1") (pinfunction "1_1") (pintype "passive"))
      (node (ref "U2") (pin "P3") (pinfunction "A2_P3") (pintype "passive"))
    )
    (net (code "5") (name "DDR3_A3") (class "Default")
      (node (ref "R4") (pin "1") (pinfunction "1_1") (pintype "passive"))
      (node (ref "U2") (pin "N2") (pinfunction "A3_N2") (pintype "passive"))
    )
    (net (code "6") (name "DDR3_A4") (class "Default")
      (node (ref "R5") (pin "1") (pinfunction "1_1") (pintype "passive"))
      (node (ref "U2") (pin "P8") (pinfunction "A4_P8") (pintype "passive"))
    )
    (net (code "7") (name "DDR3_A5") (class "Default")
      (node (ref "R6") (pin "1") (pinfunction "1_1") (pintype "passive"))
      (node (ref "U2") (pin "P2") (pinfunction "A5_P2") (pintype "passive"))
    )
    (net (code "8") (name "DDR3_A6") (class "Default")
      (node (ref "R7") (pin "1") (pinfunction "1_1") (pintype "passive"))
      (node (ref "U2") (pin "R8") (pinfunction "A6_R8") (pintype "passive"))
    )
    (net (code "9") (name "DDR3_A7") (class "Default")
      (node (ref "R8") (pin "1") (pinfunction "1_1") (pintype "passive"))
      (node (ref "U2") (pin "R2") (pinfunction "A7_R2") (pintype "passive"))
    )
    (net (code "10") (name "DDR3_A8") (class "Default")
      (node (ref "R9") (pin "1") (pinfunction "1_1") (pintype "passive"))
      (node (ref "U2") (pin "T8") (pinfunction "A8_T8") (pintype "passive"))
    )
    (net (code "11") (name "DDR3_A9") (class "Default")
      (node (ref "R10") (pin "1") (pinfunction "1_1") (pintype "passive"))
      (node (ref "U2") (pin "R3") (pinfunction "A9_R3") (pintype "passive"))
    )
    (net (code "12") (name "DDR3_A10") (class "Default")
      (node (ref "R11") (pin "1") (pinfunction "1_1") (pintype "passive"))
      (node (ref "U2") (pin "L7") (pinfunction "A10/AP_L7") (pintype "passive"))
    )
    (net (code "13") (name "DDR3_A11") (class "Default")
      (node (ref "R12") (pin "1") (pinfunction "1_1") (pintype "passive"))
      (node (ref "U2") (pin "R7") (pinfunction "A11_R7") (pintype "passive"))
    )
    (net (code "14") (name "DDR3_A12") (class "Default")
      (node (ref "R13") (pin "1") (pinfunction "1_1") (pintype "passive"))
      (node (ref "U2") (pin "N7") (pinfunction "A12/BC#_N7") (pintype "passive"))
    )
    (net (code "15") (name "DDR3_A13") (class "Default")
      (node (ref "R14") (pin "1") (pinfunction "1_1") (pintype "passive"))
      (node (ref "U2") (pin "T3") (pinfunction "A13_T3") (pintype "passive"))
    )
    (net (code "16") (name "DDR3_BA0") (class "Default")
      (node (ref "R15") (pin "1") (pinfunction "1_1") (pintype "passive"))
      (node (ref "U2") (pin "M2") (pinfunction "BA0_M2") (pintype "passive"))
    )
    (net (code "17") (name "DDR3_BA1") (class "Default")
      (node (ref "R16") (pin "1") (pinfunction "1_1") (pintype "passive"))
      (node (ref "U2") (pin "N8") (pinfunction "BA1_N8") (pintype "passive"))
    )
    (net (code "18") (name "DDR3_BA2") (class "Default")
      (node (ref "R17") (pin "1") (pinfunction "1_1") (pintype "passive"))
      (node (ref "U2") (pin "M3") (pinfunction "BA2_M3") (pintype "passive"))
    )
    (net (code "19") (name "DDR3_CAS") (class "Default")
      (node (ref "R22") (pin "1") (pinfunction "1_1") (pintype "passive"))
      (node (ref "U2") (pin "K3") (pinfunction "CAS_K3") (pintype "passive"))
    )
    (net (code "20") (name "DDR3_CKE") (class "Default")
      (node (ref "R19") (pin "1") (pinfunction "1_1") (pintype "passive"))
      (node (ref "U2") (pin "K9") (pinfunction "CKE_K9") (pintype "passive"))
    )
    (net (code "21") (name "DDR3_CK_N") (class "Default")
      (node (ref "R27") (pin "1") (pinfunction "1_1") (pintype "passive"))
      (node (ref "U2") (pin "K7") (pinfunction "CK_K7") (pintype "passive"))
    )
    (net (code "22") (name "DDR3_CK_P") (class "Default")
      (node (ref "R26") (pin "2") (pinfunction "2_2") (pintype "passive"))
      (node (ref "U2") (pin "J7") (pinfunction "CK_J7") (pintype "passive"))
    )
    (net (code "23") (name "DDR3_CS") (class "Default")
      (node (ref "R20") (pin "1") (pinfunction "1_1") (pintype "passive"))
      (node (ref "R29") (pin "1") (pinfunction "1_1") (pintype "passive"))
      (node (ref "U2") (pin "L2") (pinfunction "CS_L2") (pintype "passive"))
    )
    (net (code "24") (name "DDR3_DQ0") (class "Default")
      (node (ref "U2") (pin "E3") (pinfunction "DQ0_E3") (pintype "passive"))
    )
    (net (code "25") (name "DDR3_DQ1") (class "Default")
      (node (ref "U2") (pin "F7") (pinfunction "DQ1_F7") (pintype "passive"))
    )
    (net (code "26") (name "DDR3_DQ2") (class "Default")
      (node (ref "U2") (pin "F2") (pinfunction "DQ2_F2") (pintype "passive"))
    )
    (net (code "27") (name "DDR3_DQ3") (class "Default")
      (node (ref "U2") (pin "F8") (pinfunction "DQ3_F8") (pintype "passive"))
    )
    (net (code "28") (name "DDR3_DQ4") (class "Default")
      (node (ref "U2") (pin "H3") (pinfunction "DQ4_H3") (pintype "passive"))
    )
    (net (code "29") (name "DDR3_DQ5") (class "Default")
      (node (ref "U2") (pin "H8") (pinfunction "DQ5_H8") (pintype "passive"))
    )
    (net (code "30") (name "DDR3_DQ6") (class "Default")
      (node (ref "U2") (pin "G2") (pinfunction "DQ6_G2") (pintype "passive"))
    )
    (net (code "31") (name "DDR3_DQ7") (class "Default")
      (node (ref "U2") (pin "H7") (pinfunction "DQ7_H7") (pintype "passive"))
    )
    (net (code "32") (name "DDR3_DQ8") (class "Default")
      (node (ref "U2") (pin "D7") (pinfunction "DQ8_D7") (pintype "passive"))
    )
    (net (code "33") (name "DDR3_DQ9") (class "Default")
      (node (ref "U2") (pin "C3") (pinfunction "DQ9_C3") (pintype "passive"))
    )
    (net (code "34") (name "DDR3_DQ10") (class "Default")
      (node (ref "U2") (pin "C8") (pinfunction "DQ10_C8") (pintype "passive"))
    )
    (net (code "35") (name "DDR3_DQ11") (class "Default")
      (node (ref "U2") (pin "C2") (pinfunction "DQ11_C2") (pintype "passive"))
    )
    (net (code "36") (name "DDR3_DQ12") (class "Default")
      (node (ref "U2") (pin "A7") (pinfunction "DQ12_A7") (pintype "passive"))
    )
    (net (code "37") (name "DDR3_DQ13") (class "Default")
      (node (ref "U2") (pin "A2") (pinfunction "DQ13_A2") (pintype "passive"))
    )
    (net (code "38") (name "DDR3_DQ14") (class "Default")
      (node (ref "U2") (pin "B8") (pinfunction "DQ14_B8") (pintype "passive"))
    )
    (net (code "39") (name "DDR3_DQ15") (class "Default")
      (node (ref "U2") (pin "A3") (pinfunction "DQ15_A3") (pintype "passive"))
    )
    (net (code "40") (name "DDR3_LDM") (class "Default")
      (node (ref "U2") (pin "E7") (pinfunction "LDM_E7") (pintype "passive"))
    )
    (net (code "41") (name "DDR3_LDQS_N") (class "Default")
      (node (ref "U2") (pin "G3") (pinfunction "LDQS_G3") (pintype "passive"))
    )
    (net (code "42") (name "DDR3_LDQS_P") (class "Default")
      (node (ref "U2") (pin "F3") (pinfunction "LDQS_F3") (pintype "passive"))
    )
    (net (code "43") (name "DDR3_ODT") (class "Default")
      (node (ref "R24") (pin "1") (pinfunction "1_1") (pintype "passive"))
      (node (ref "U2") (pin "K1") (pinfunction "ODT_K1") (pintype "passive"))
    )
    (net (code "44") (name "DDR3_RAS") (class "Default")
      (node (ref "R21") (pin "1") (pinfunction "1_1") (pintype "passive"))
      (node (ref "U2") (pin "J3") (pinfunction "RAS_J3") (pintype "passive"))
    )
    (net (code "45") (name "DDR3_RESET") (class "Default")
      (node (ref "R25") (pin "2") (pinfunction "2_2") (pintype "passive"))
      (node (ref "U2") (pin "T2") (pinfunction "RESET_T2") (pintype "passive"))
    )
    (net (code "46") (name "DDR3_UDM") (class "Default")
      (node (ref "U2") (pin "D3") (pinfunction "UDM_D3") (pintype "passive"))
    )
    (net (code "47") (name "DDR3_UDQS_N") (class "Default")
      (node (ref "U2") (pin "B7") (pinfunction "UDQS_B7") (pintype "passive"))
    )
    (net (code "48") (name "DDR3_UDQS_P") (class "Default")
      (node (ref "U2") (pin "C7") (pinfunction "UDQS_C7") (pintype "passive"))
    )
    (net (code "49") (name "DDR3_WE") (class "Default")
      (node (ref "R23") (pin "1") (pinfunction "1_1") (pintype "passive"))
      (node (ref "U2") (pin "L3") (pinfunction "WE_L3") (pintype "passive"))
    )
    (net (code "50") (name "GND") (class "Default")
      (node (ref "C117") (pin "1") (pinfunction "1_1") (pintype "passive"))
      (node (ref "C152") (pin "1") (pinfunction "1_1") (pintype "passive"))
      (node (ref "C153") (pin "1") (pinfunction "1_1") (pintype "passive"))
      (node (ref "C154") (pin "1") (pinfunction "1_1") (pintype "passive"))
      (node (ref "C155") (pin "1") (pinfunction "1_1") (pintype "passive"))
      (node (ref "C158") (pin "1") (pinfunction "1_1") (pintype "passive"))
      (node (ref "C159") (pin "1") (pinfunction "1_1") (pintype "passive"))
      (node (ref "C16") (pin "1") (pinfunction "1_1") (pintype "passive"))
      (node (ref "C160") (pin "1") (pinfunction "1_1") (pintype "passive"))
      (node (ref "C161") (pin "1") (pinfunction "1_1") (pintype "passive"))
      (node (ref "C162") (pin "1") (pinfunction "1_1") (pintype "passive"))
      (node (ref "C163") (pin "1") (pinfunction "1_1") (pintype "passive"))
      (node (ref "C164") (pin "1") (pinfunction "1_1") (pintype "passive"))
      (node (ref "C167") (pin "1") (pinfunction "1_1") (pintype "passive"))
      (node (ref "C17") (pin "1") (pinfunction "1_1") (pintype "passive"))
      (node (ref "C170") (pin "1") (pinfunction "1_1") (pintype "passive"))
      (node (ref "C171") (pin "1") (pinfunction "1_1") (pintype "passive"))
      (node (ref "C172") (pin "1") (pinfunction "1_1") (pintype "passive"))
      (node (ref "C173") (pin "1") (pinfunction "1_1") (pintype "passive"))
      (node (ref "C174") (pin "1") (pinfunction "1_1") (pintype "passive"))
      (node (ref "C175") (pin "1") (pinfunction "1_1") (pintype "passive"))
      (node (ref "C176") (pin "1") (pinfunction "1_1") (pintype "passive"))
      (node (ref "C18") (pin "1") (pinfunction "1_1") (pintype "passive"))
      (node (ref "C181") (pin "1") (pinfunction "1_1") (pintype "passive"))
      (node (ref "C182") (pin "1") (pinfunction "1_1") (pintype "passive"))
      (node (ref "C183") (pin "1") (pinfunction "1_1") (pintype "passive"))
      (node (ref "C19") (pin "1") (pinfunction "1_1") (pintype "passive"))
      (node (ref "C20") (pin "1") (pinfunction "1_1") (pintype "passive"))
      (node (ref "C21") (pin "1") (pinfunction "1_1") (pintype "passive"))
      (node (ref "C22") (pin "1") (pinfunction "1_1") (pintype "passive"))
      (node (ref "C23") (pin "1") (pinfunction "1_1") (pintype "passive"))
      (node (ref "C24") (pin "1") (pinfunction "1_1") (pintype "passive"))
      (node (ref "C26") (pin "1") (pinfunction "1_1") (pintype "passive"))
      (node (ref "C27") (pin "1") (pinfunction "1_1") (pintype "passive"))
      (node (ref "C28") (pin "1") (pinfunction "1_1") (pintype "passive"))
      (node (ref "C29") (pin "1") (pinfunction "1_1") (pintype "passive"))
      (node (ref "C30") (pin "1") (pinfunction "1_1") (pintype "passive"))
      (node (ref "C31") (pin "1") (pinfunction "1_1") (pintype "passive"))
      (node (ref "C32") (pin "1") (pinfunction "1_1") (pintype "passive"))
      (node (ref "C39") (pin "1") (pinfunction "1_1") (pintype "passive"))
      (node (ref "C42") (pin "1") (pinfunction "1_1") (pintype "passive"))
      (node (ref "C43") (pin "1") (pinfunction "1_1") (pintype "passive"))
      (node (ref "C44") (pin "1") (pinfunction "1_1") (pintype "passive"))
      (node (ref "C45") (pin "1") (pinfunction "1_1") (pintype "passive"))
      (node (ref "C49") (pin "1") (pinfunction "1_1") (pintype "passive"))
      (node (ref "C50") (pin "1") (pinfunction "1_1") (pintype "passive"))
      (node (ref "C57") (pin "1") (pinfunction "1_1") (pintype "passive"))
      (node (ref "C58") (pin "1") (pinfunction "1_1") (pintype "passive"))
      (node (ref "C60") (pin "1") (pinfunction "1_1") (pintype "passive"))
      (node (ref "C74") (pin "1") (pinfunction "1_1") (pintype "passive"))
      (node (ref "C75") (pin "1") (pinfunction "1_1") (pintype "passive"))
      (node (ref "R25") (pin "1") (pinfunction "1_1") (pintype "passive"))
      (node (ref "R28") (pin "2") (pinfunction "2_2") (pintype "passive"))
      (node (ref "R29") (pin "2") (pinfunction "2_2") (pintype "passive"))
      (node (ref "R32") (pin "2") (pinfunction "2_2") (pintype "passive"))
      (node (ref "U2") (pin "A9") (pinfunction "VSS_A9") (pintype "passive"))
      (node (ref "U2") (pin "B1") (pinfunction "VSSQ_B1") (pintype "passive"))
      (node (ref "U2") (pin "B3") (pinfunction "VSS_B3") (pintype "passive"))
      (node (ref "U2") (pin "B9") (pinfunction "VSSQ_B9") (pintype "passive"))
      (node (ref "U2") (pin "D1") (pinfunction "VSSQ_D1") (pintype "passive"))
      (node (ref "U2") (pin "D8") (pinfunction "VSSQ_D8") (pintype "passive"))
      (node (ref "U2") (pin "E1") (pinfunction "VSS_E1") (pintype "passive"))
      (node (ref "U2") (pin "E2") (pinfunction "VSSQ_E2") (pintype "passive"))
      (node (ref "U2") (pin "E8") (pinfunction "VSSQ_E8") (pintype "passive"))
      (node (ref "U2") (pin "F9") (pinfunction "VSSQ_F9") (pintype "passive"))
      (node (ref "U2") (pin "G1") (pinfunction "VSSQ_G1") (pintype "passive"))
      (node (ref "U2") (pin "G8") (pinfunction "VSS_G8") (pintype "passive"))
      (node (ref "U2") (pin "G9") (pinfunction "VSSQ_G9") (pintype "passive"))
      (node (ref "U2") (pin "J2") (pinfunction "VSS_J2") (pintype "passive"))
      (node (ref "U2") (pin "J8") (pinfunction "VSS_J8") (pintype "passive"))
      (node (ref "U2") (pin "M1") (pinfunction "VSS_M1") (pintype "passive"))
      (node (ref "U2") (pin "M9") (pinfunction "VSS_M9") (pintype "passive"))
      (node (ref "U2") (pin "P1") (pinfunction "VSS_P1") (pintype "passive"))
      (node (ref "U2") (pin "P9") (pinfunction "VSS_P9") (pintype "passive"))
      (node (ref "U2") (pin "T1") (pinfunction "VSS_T1") (pintype "passive"))
      (node (ref "U2") (pin "T9") (pinfunction "VSS_T9") (pintype "passive"))
      (node (ref "U3") (pin "11") (pinfunction "EP_11") (pintype "passive"))
      (node (ref "U3") (pin "4") (pinfunction "PGND_4") (pintype "passive"))
      (node (ref "U3") (pin "8") (pinfunction "GND_8") (pintype "passive"))
    )
    (net (code "51") (name "Net-(R26-Pad1)") (class "Default")
      (node (ref "R26") (pin "1") (pinfunction "1_1") (pintype "passive"))
      (node (ref "R27") (pin "2") (pinfunction "2_2") (pintype "passive"))
    )
    (net (code "52") (name "Net-(U2-ZQ)") (class "Default")
      (node (ref "R28") (pin "1") (pinfunction "1_1") (pintype "passive"))
      (node (ref "U2") (pin "L8") (pinfunction "ZQ_L8") (pintype "passive"))
    )
    (net (code "53") (name "Net-(U3-REFIN)") (class "Default")
      (node (ref "C26") (pin "2") (pinfunction "2_2") (pintype "passive"))
      (node (ref "R31") (pin "2") (pinfunction "2_2") (pintype "passive"))
      (node (ref "R32") (pin "1") (pinfunction "1_1") (pintype "passive"))
      (node (ref "U3") (pin "1") (pinfunction "REFIN_1") (pintype "passive"))
    )
    (net (code "54") (name "PG_1V5") (class "Default")
      (node (ref "U3") (pin "7") (pinfunction "EN_7") (pintype "passive"))
    )
    (net (code "55") (name "PG_DDR3") (class "Default")
      (node (ref "U3") (pin "9") (pinfunction "PGOOD_9") (pintype "passive"))
    )
    (net (code "56") (name "VCC1V5") (class "Default")
      (node (ref "C152") (pin "2") (pinfunction "2_2") (pintype "passive"))
      (node (ref "C153") (pin "2") (pinfunction "2_2") (pintype "passive"))
      (node (ref "C154") (pin "2") (pinfunction "2_2") (pintype "passive"))
      (node (ref "C155") (pin "2") (pinfunction "2_2") (pintype "passive"))
      (node (ref "C158") (pin "2") (pinfunction "2_2") (pintype "passive"))
      (node (ref "C159") (pin "2") (pinfunction "2_2") (pintype "passive"))
      (node (ref "C160") (pin "2") (pinfunction "2_2") (pintype "passive"))
      (node (ref "C161") (pin "2") (pinfunction "2_2") (pintype "passive"))
      (node (ref "C162") (pin "2") (pinfunction "2_2") (pintype "passive"))
      (node (ref "C163") (pin "2") (pinfunction "2_2") (pintype "passive"))
      (node (ref "C164") (pin "2") (pinfunction "2_2") (pintype "passive"))
      (node (ref "C167") (pin "2") (pinfunction "2_2") (pintype "passive"))
      (node (ref "C170") (pin "2") (pinfunction "2_2") (pintype "passive"))
      (node (ref "C27") (pin "2") (pinfunction "2_2") (pintype "passive"))
      (node (ref "C28") (pin "2") (pinfunction "2_2") (pintype "passive"))
      (node (ref "C57") (pin "2") (pinfunction "2_2") (pintype "passive"))
      (node (ref "C58") (pin "2") (pinfunction "2_2") (pintype "passive"))
      (node (ref "C60") (pin "2") (pinfunction "2_2") (pintype "passive"))
      (node (ref "C74") (pin "2") (pinfunction "2_2") (pintype "passive"))
      (node (ref "C75") (pin "2") (pinfunction "2_2") (pintype "passive"))
      (node (ref "R31") (pin "1") (pinfunction "1_1") (pintype "passive"))
      (node (ref "U2") (pin "A1") (pinfunction "VDDQ_A1") (pintype "passive"))
      (node (ref "U2") (pin "A8") (pinfunction "VDDQ_A8") (pintype "passive"))
      (node (ref "U2") (pin "B2") (pinfunction "VDD_B2") (pintype "passive"))
      (node (ref "U2") (pin "C1") (pinfunction "VDDQ_C1") (pintype "passive"))
      (node (ref "U2") (pin "C9") (pinfunction "VDDQ_C9") (pintype "passive"))
      (node (ref "U2") (pin "D2") (pinfunction "VDDQ_D2") (pintype "passive"))
      (node (ref "U2") (pin "D9") (pinfunction "VDD_D9") (pintype "passive"))
      (node (ref "U2") (pin "E9") (pinfunction "VDDQ_E9") (pintype "passive"))
      (node (ref "U2") (pin "F1") (pinfunction "VDDQ_F1") (pintype "passive"))
      (node (ref "U2") (pin "G7") (pinfunction "VDD_G7") (pintype "passive"))
      (node (ref "U2") (pin "H2") (pinfunction "VDDQ_H2") (pintype "passive"))
      (node (ref "U2") (pin "H9") (pinfunction "VDDQ_H9") (pintype "passive"))
      (node (ref "U2") (pin "K2") (pinfunction "VDD_K2") (pintype "passive"))
      (node (ref "U2") (pin "K8") (pinfunction "VDD_K8") (pintype "passive"))
      (node (ref "U2") (pin "N1") (pinfunction "VDD_N1") (pintype "passive"))
      (node (ref "U2") (pin "N9") (pinfunction "VDD_N9") (pintype "passive"))
      (node (ref "U2") (pin "R1") (pinfunction "VDD_R1") (pintype "passive"))
      (node (ref "U2") (pin "R9") (pinfunction "VDD_R9") (pintype "passive"))
      (node (ref "U3") (pin "2") (pinfunction "VLDOIN_2") (pintype "passive"))
    )
    (net (code "57") (name "VREF0V75") (class "Default")
      (node (ref "C50") (pin "2") (pinfunction "2_2") (pintype "passive"))
      (node (ref "U2") (pin "H1") (pinfunction "VREFDQ_H1") (pintype "passive"))
      (node (ref "U2") (pin "M8") (pinfunction "VREFCA_M8") (pintype "passive"))
      (node (ref "U3") (pin "6") (pinfunction "REFOUT_6") (pintype "passive"))
    )
    (net (code "58") (name "VTT0V75") (class "Default")
      (node (ref "C16") (pin "2") (pinfunction "2_2") (pintype "passive"))
      (node (ref "C17") (pin "2") (pinfunction "2_2") (pintype "passive"))
      (node (ref "C171") (pin "2") (pinfunction "2_2") (pintype "passive"))
      (node (ref "C172") (pin "2") (pinfunction "2_2") (pintype "passive"))
      (node (ref "C173") (pin "2") (pinfunction "2_2") (pintype "passive"))
      (node (ref "C174") (pin "2") (pinfunction "2_2") (pintype "passive"))
      (node (ref "C175") (pin "2") (pinfunction "2_2") (pintype "passive"))
      (node (ref "C176") (pin "2") (pinfunction "2_2") (pintype "passive"))
      (node (ref "C18") (pin "2") (pinfunction "2_2") (pintype "passive"))
      (node (ref "C181") (pin "2") (pinfunction "2_2") (pintype "passive"))
      (node (ref "C182") (pin "2") (pinfunction "2_2") (pintype "passive"))
      (node (ref "C183") (pin "2") (pinfunction "2_2") (pintype "passive"))
      (node (ref "C19") (pin "2") (pinfunction "2_2") (pintype "passive"))
      (node (ref "C20") (pin "2") (pinfunction "2_2") (pintype "passive"))
      (node (ref "C21") (pin "2") (pinfunction "2_2") (pintype "passive"))
      (node (ref "C22") (pin "2") (pinfunction "2_2") (pintype "passive"))
      (node (ref "C23") (pin "2") (pinfunction "2_2") (pintype "passive"))
      (node (ref "C24") (pin "2") (pinfunction "2_2") (pintype "passive"))
      (node (ref "C29") (pin "2") (pinfunction "2_2") (pintype "passive"))
      (node (ref "C30") (pin "2") (pinfunction "2_2") (pintype "passive"))
      (node (ref "C31") (pin "2") (pinfunction "2_2") (pintype "passive"))
      (node (ref "C32") (pin "2") (pinfunction "2_2") (pintype "passive"))
      (node (ref "C39") (pin "2") (pinfunction "2_2") (pintype "passive"))
      (node (ref "C42") (pin "2") (pinfunction "2_2") (pintype "passive"))
      (node (ref "C43") (pin "2") (pinfunction "2_2") (pintype "passive"))
      (node (ref "C44") (pin "2") (pinfunction "2_2") (pintype "passive"))
      (node (ref "C45") (pin "2") (pinfunction "2_2") (pintype "passive"))
      (node (ref "C49") (pin "2") (pinfunction "2_2") (pintype "passive"))
      (node (ref "R1") (pin "2") (pinfunction "2_2") (pintype "passive"))
      (node (ref "R10") (pin "2") (pinfunction "2_2") (pintype "passive"))
      (node (ref "R11") (pin "2") (pinfunction "2_2") (pintype "passive"))
      (node (ref "R12") (pin "2") (pinfunction "2_2") (pintype "passive"))
      (node (ref "R13") (pin "2") (pinfunction "2_2") (pintype "passive"))
      (node (ref "R14") (pin "2") (pinfunction "2_2") (pintype "passive"))
      (node (ref "R15") (pin "2") (pinfunction "2_2") (pintype "passive"))
      (node (ref "R16") (pin "2") (pinfunction "2_2") (pintype "passive"))
      (node (ref "R17") (pin "2") (pinfunction "2_2") (pintype "passive"))
      (node (ref "R19") (pin "2") (pinfunction "2_2") (pintype "passive"))
      (node (ref "R2") (pin "2") (pinfunction "2_2") (pintype "passive"))
      (node (ref "R20") (pin "2") (pinfunction "2_2") (pintype "passive"))
      (node (ref "R21") (pin "2") (pinfunction "2_2") (pintype "passive"))
      (node (ref "R22") (pin "2") (pinfunction "2_2") (pintype "passive"))
      (node (ref "R23") (pin "2") (pinfunction "2_2") (pintype "passive"))
      (node (ref "R24") (pin "2") (pinfunction "2_2") (pintype "passive"))
      (node (ref "R3") (pin "2") (pinfunction "2_2") (pintype "passive"))
      (node (ref "R4") (pin "2") (pinfunction "2_2") (pintype "passive"))
      (node (ref "R5") (pin "2") (pinfunction "2_2") (pintype "passive"))
      (node (ref "R6") (pin "2") (pinfunction "2_2") (pintype "passive"))
      (node (ref "R7") (pin "2") (pinfunction "2_2") (pintype "passive"))
      (node (ref "R8") (pin "2") (pinfunction "2_2") (pintype "passive"))
      (node (ref "R9") (pin "2") (pinfunction "2_2") (pintype "passive"))
      (node (ref "U3") (pin "3") (pinfunction "VO_3") (pintype "passive"))
      (node (ref "U3") (pin "5") (pinfunction "VOSNS_5") (pintype "passive"))
    )
    (net (code "59") (name "unconnected-(U2-NC-PadJ1)") (class "Default")
      (node (ref "U2") (pin "J1") (pinfunction "NC_J1") (pintype "passive+no_connect"))
    )
    (net (code "60") (name "unconnected-(U2-NC-PadJ9)") (class "Default")
      (node (ref "U2") (pin "J9") (pinfunction "NC_J9") (pintype "passive+no_connect"))
    )
    (net (code "61") (name "unconnected-(U2-NC-PadL1)") (class "Default")
      (node (ref "U2") (pin "L1") (pinfunction "NC_L1") (pintype "passive+no_connect"))
    )
    (net (code "62") (name "unconnected-(U2-NC-PadL9)") (class "Default")
      (node (ref "U2") (pin "L9") (pinfunction "NC_L9") (pintype "passive+no_connect"))
    )
    (net (code "63") (name "unconnected-(U2-NC-PadM7)") (class "Default")
      (node (ref "U2") (pin "M7") (pinfunction "NC_M7") (pintype "passive+no_connect"))
    )
    (net (code "64") (name "unconnected-(U2-NC-PadT7)") (class "Default")
      (node (ref "U2") (pin "T7") (pinfunction "NC_T7") (pintype "passive+no_connect"))
    )
  )
)
